# DIOT_Kasli_Adapter.net
KiCad netlist of a schematic drawn in Altium Designer
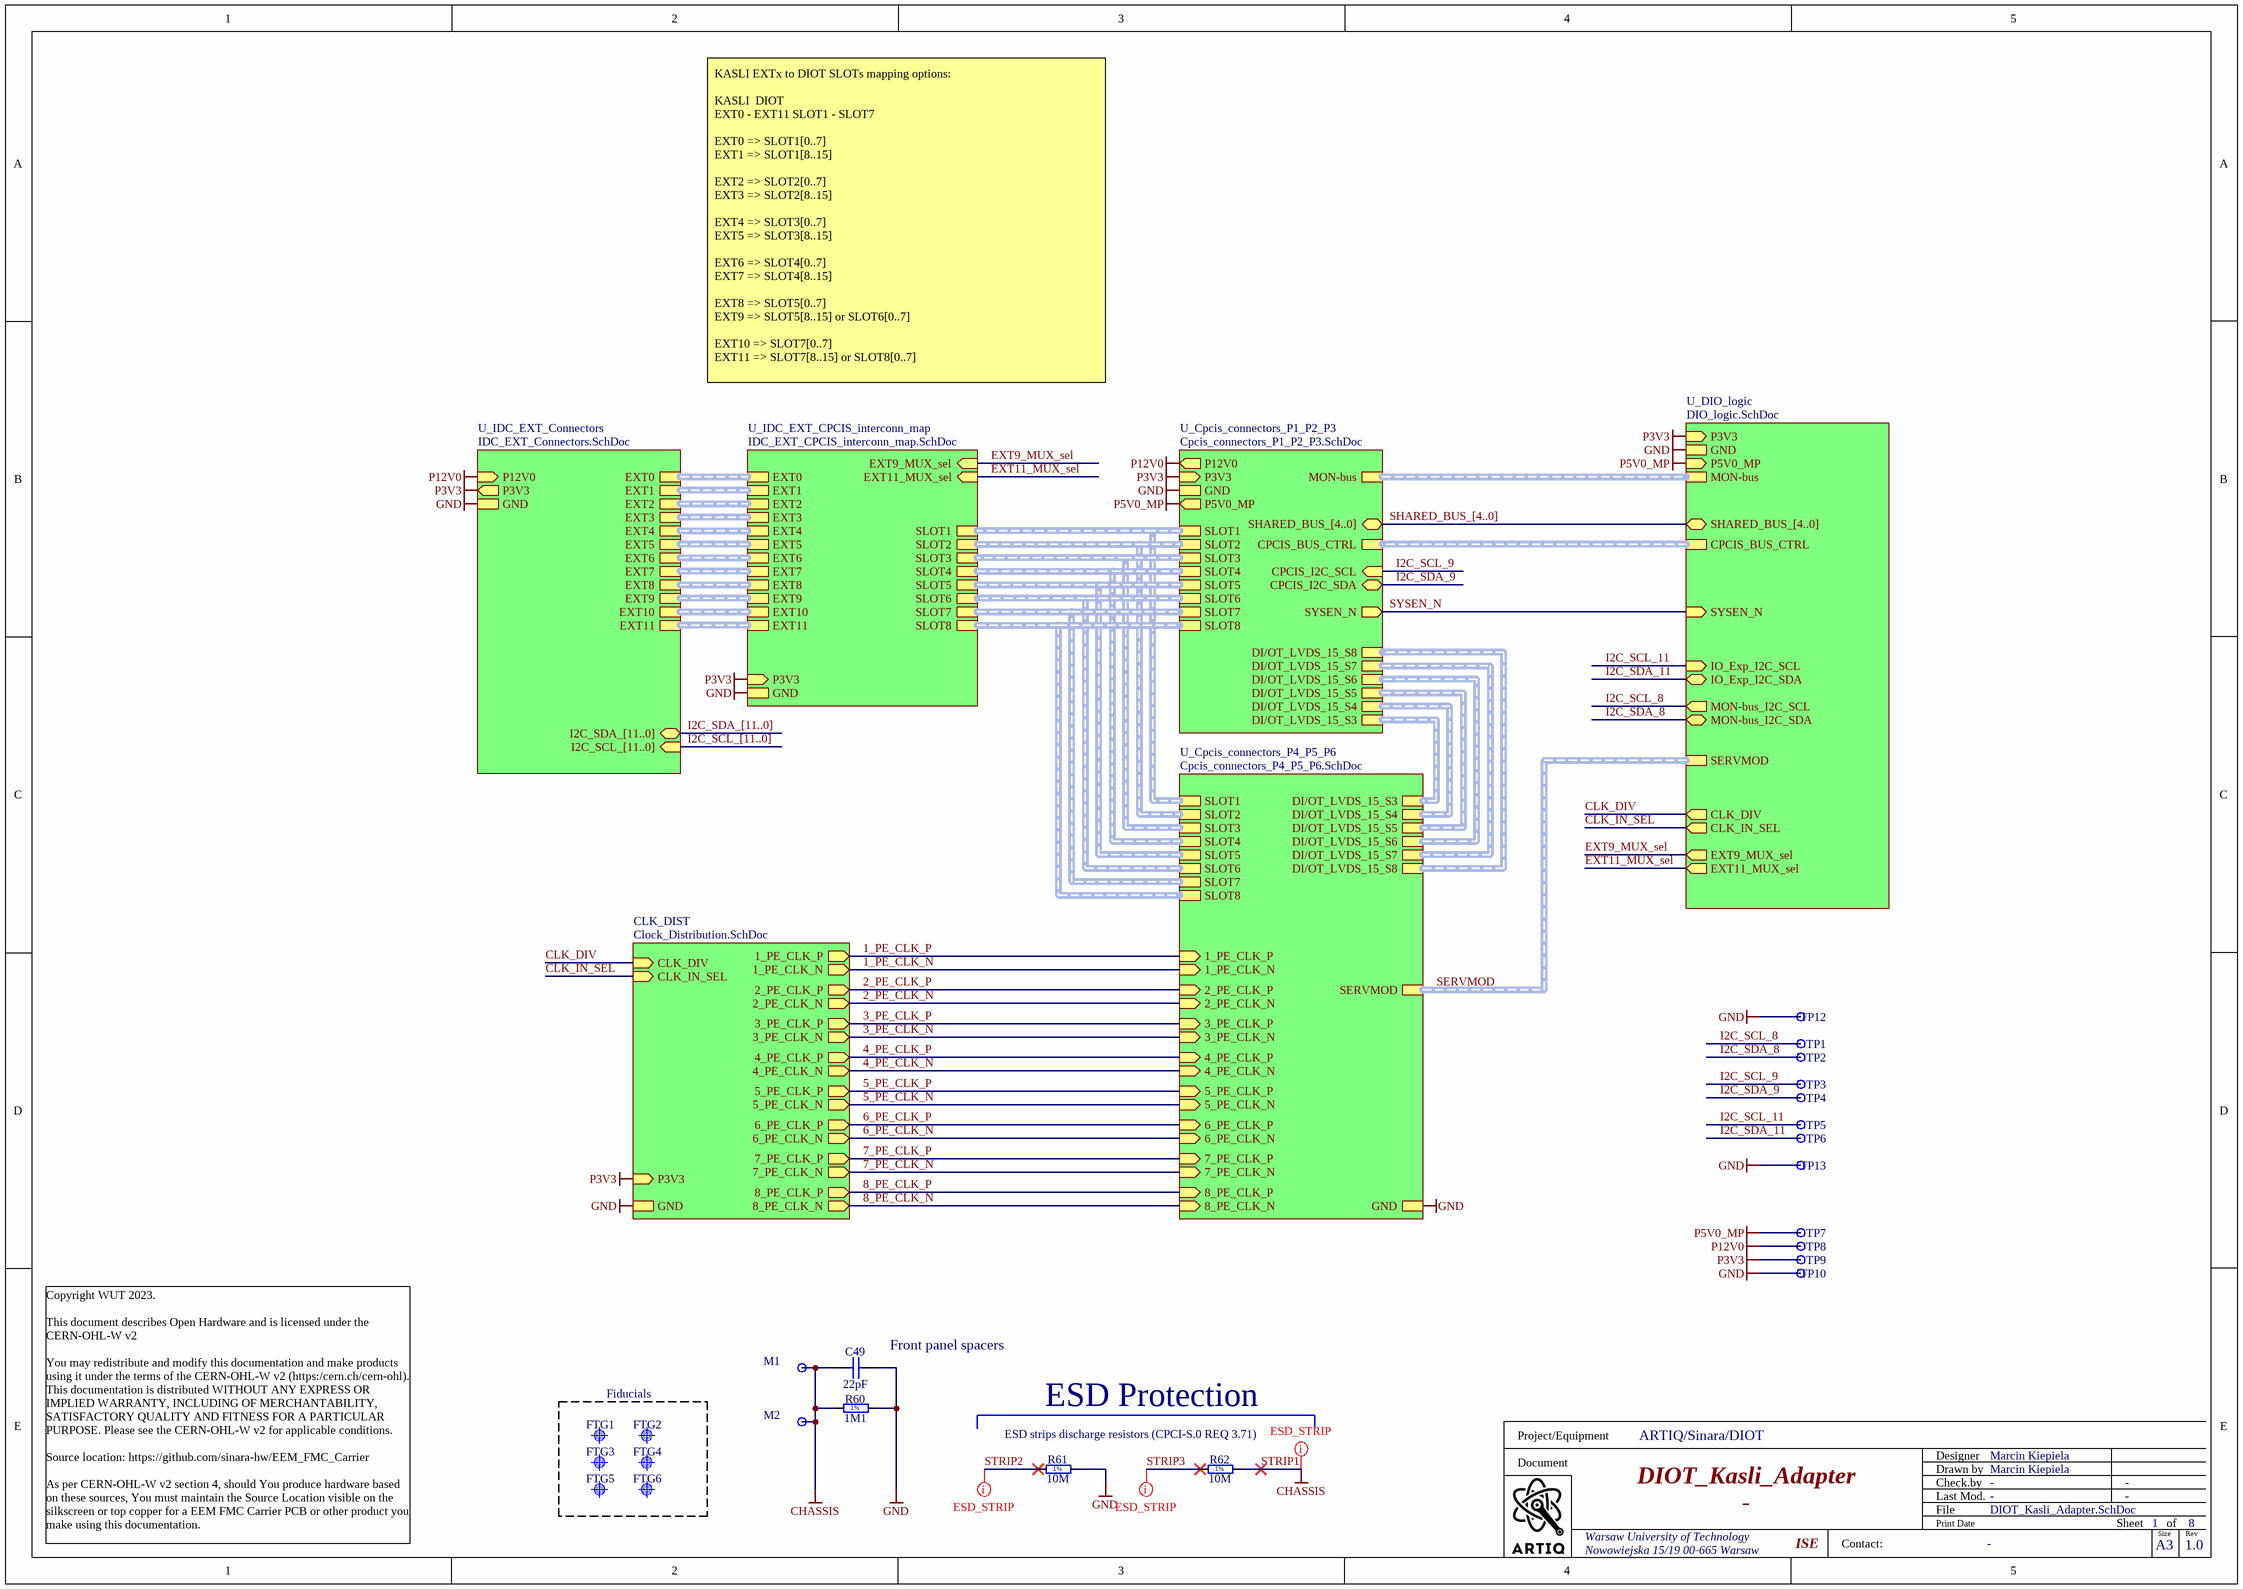
[diagram p0: DIOT_Kasli_Adapter.SchDoc]

(export (version "E")
  (design (tool "Eeschema 10.0.6"))
  (components
    (comp (ref "C49")
      (value "22pF")
      (footprint "CAPC1005X55N")
      (description "Non-polarised capacitor")
      (fields
        (field (name "PART NUMBER") "CC0402_22PF_50V_5%_C0G")
        (field (name "VOLTAGE") "50V")
        (field (name "AUTHOR") "CERN DEM JLC")
      )
      (libsource (lib "Capacitors") (part "Capacitor - non polarized"))
    )
    (comp (ref "FTG1")
      (value "Use only in PCB")
      (footprint "FIDUCIAL_TOP_S100-200")
      (description "Fiducial Target")
      (fields (field (name "PART NUMBER") "FIDUCIAL_TARGET_S100-200") (field (name "AUTHOR") "CERN DEM JLC"))
      (libsource (lib "Eletro-mechanical") (part "Fiducial Target"))
    )
    (comp (ref "FTG2")
      (value "Use only in PCB")
      (footprint "FIDUCIAL_TOP_S100-200")
      (description "Fiducial Target")
      (fields (field (name "PART NUMBER") "FIDUCIAL_TARGET_S100-200") (field (name "AUTHOR") "CERN DEM JLC"))
      (libsource (lib "Eletro-mechanical") (part "Fiducial Target"))
    )
    (comp (ref "FTG3")
      (value "Use only in PCB")
      (footprint "FIDUCIAL_TOP_S100-200")
      (description "Fiducial Target")
      (fields (field (name "PART NUMBER") "FIDUCIAL_TARGET_S100-200") (field (name "AUTHOR") "CERN DEM JLC"))
      (libsource (lib "Eletro-mechanical") (part "Fiducial Target"))
    )
    (comp (ref "FTG4")
      (value "Use only in PCB")
      (footprint "FIDUCIAL_TOP_S100-200")
      (description "Fiducial Target")
      (fields (field (name "PART NUMBER") "FIDUCIAL_TARGET_S100-200") (field (name "AUTHOR") "CERN DEM JLC"))
      (libsource (lib "Eletro-mechanical") (part "Fiducial Target"))
    )
    (comp (ref "FTG5")
      (value "Use only in PCB")
      (footprint "FIDUCIAL_TOP_S100-200")
      (description "Fiducial Target")
      (fields (field (name "PART NUMBER") "FIDUCIAL_TARGET_S100-200") (field (name "AUTHOR") "CERN DEM JLC"))
      (libsource (lib "Eletro-mechanical") (part "Fiducial Target"))
    )
    (comp (ref "FTG6")
      (value "Use only in PCB")
      (footprint "FIDUCIAL_TOP_S100-200")
      (description "Fiducial Target")
      (fields (field (name "PART NUMBER") "FIDUCIAL_TARGET_S100-200") (field (name "AUTHOR") "CERN DEM JLC"))
      (libsource (lib "Eletro-mechanical") (part "Fiducial Target"))
    )
    (comp (ref "M1")
      (value "Plated Hole")
      (footprint "MTG300_600")
      (description "Single Terminal Socket")
      (fields (field (name "PART NUMBER") "PLATED_HOLE3.0_PAD6.0") (field (name "AUTHOR") "CERN DEM JLC"))
      (libsource (lib "Eletro-mechanical") (part "Single Terminal Socket"))
    )
    (comp (ref "M2")
      (value "Plated Hole")
      (footprint "MTG300_600")
      (description "Single Terminal Socket")
      (fields (field (name "PART NUMBER") "PLATED_HOLE3.0_PAD6.0") (field (name "AUTHOR") "CERN DEM JLC"))
      (libsource (lib "Eletro-mechanical") (part "Single Terminal Socket"))
    )
    (comp (ref "R60")
      (value "1M1")
      (footprint "RESC2012X60N")
      (description "Resistor - 1%")
      (fields
        (field (name "PART NUMBER") "R0805_1M1_1%_0.125W_100PPM")
        (field (name "POWER") "0.125W")
        (field (name "AUTHOR") "CERN DEM JLC")
      )
      (libsource (lib "Resistors") (part "Resistor - 1%"))
    )
    (comp (ref "R61")
      (value "10M")
      (footprint "RESC2113X55N")
      (description "Resistor - 1%")
      (fields
        (field (name "PART NUMBER") "R0805_10M_1%_0.125W_100PPM_VISHAY_CRCW e3")
        (field (name "POWER") "0.125W")
        (field (name "AUTHOR") "CERN DEM BC")
      )
      (libsource (lib "Resistors") (part "Resistor - 1%"))
    )
    (comp (ref "R62")
      (value "10M")
      (footprint "RESC2113X55N")
      (description "Resistor - 1%")
      (fields
        (field (name "PART NUMBER") "R0805_10M_1%_0.125W_100PPM_VISHAY_CRCW e3")
        (field (name "POWER") "0.125W")
        (field (name "AUTHOR") "CERN DEM BC")
      )
      (libsource (lib "Resistors") (part "Resistor - 1%"))
    )
    (comp (ref "TP1")
      (value "P3V3")
      (footprint "TPS127")
      (description "Test Point")
      (fields (field (name "PART NUMBER") "SMD_PAD_1.27X1.27MM") (field (name "AUTHOR") "CERN DEM JLC"))
      (libsource (lib "Eletro-mechanical") (part "Test Point"))
    )
    (comp (ref "TP2")
      (value "P3V3")
      (footprint "TPS127")
      (description "Test Point")
      (fields (field (name "PART NUMBER") "SMD_PAD_1.27X1.27MM") (field (name "AUTHOR") "CERN DEM JLC"))
      (libsource (lib "Eletro-mechanical") (part "Test Point"))
    )
    (comp (ref "TP3")
      (value "P3V3")
      (footprint "TPS127")
      (description "Test Point")
      (fields (field (name "PART NUMBER") "SMD_PAD_1.27X1.27MM") (field (name "AUTHOR") "CERN DEM JLC"))
      (libsource (lib "Eletro-mechanical") (part "Test Point"))
    )
    (comp (ref "TP4")
      (value "P3V3")
      (footprint "TPS127")
      (description "Test Point")
      (fields (field (name "PART NUMBER") "SMD_PAD_1.27X1.27MM") (field (name "AUTHOR") "CERN DEM JLC"))
      (libsource (lib "Eletro-mechanical") (part "Test Point"))
    )
    (comp (ref "TP5")
      (value "P3V3")
      (footprint "TPS127")
      (description "Test Point")
      (fields (field (name "PART NUMBER") "SMD_PAD_1.27X1.27MM") (field (name "AUTHOR") "CERN DEM JLC"))
      (libsource (lib "Eletro-mechanical") (part "Test Point"))
    )
    (comp (ref "TP6")
      (value "P3V3")
      (footprint "TPS127")
      (description "Test Point")
      (fields (field (name "PART NUMBER") "SMD_PAD_1.27X1.27MM") (field (name "AUTHOR") "CERN DEM JLC"))
      (libsource (lib "Eletro-mechanical") (part "Test Point"))
    )
    (comp (ref "TP7")
      (value "P3V3")
      (footprint "TPS127")
      (description "Test Point")
      (fields (field (name "PART NUMBER") "SMD_PAD_1.27X1.27MM") (field (name "AUTHOR") "CERN DEM JLC"))
      (libsource (lib "Eletro-mechanical") (part "Test Point"))
    )
    (comp (ref "TP8")
      (value "P3V3")
      (footprint "TPS127")
      (description "Test Point")
      (fields (field (name "PART NUMBER") "SMD_PAD_1.27X1.27MM") (field (name "AUTHOR") "CERN DEM JLC"))
      (libsource (lib "Eletro-mechanical") (part "Test Point"))
    )
    (comp (ref "TP9")
      (value "P3V3")
      (footprint "TPS127")
      (description "Test Point")
      (fields (field (name "PART NUMBER") "SMD_PAD_1.27X1.27MM") (field (name "AUTHOR") "CERN DEM JLC"))
      (libsource (lib "Eletro-mechanical") (part "Test Point"))
    )
    (comp (ref "TP10")
      (value "P3V3")
      (footprint "TPS127")
      (description "Test Point")
      (fields (field (name "PART NUMBER") "SMD_PAD_1.27X1.27MM") (field (name "AUTHOR") "CERN DEM JLC"))
      (libsource (lib "Eletro-mechanical") (part "Test Point"))
    )
    (comp (ref "TP12")
      (value "P3V3")
      (footprint "TPS127")
      (description "Test Point")
      (fields (field (name "PART NUMBER") "SMD_PAD_1.27X1.27MM") (field (name "AUTHOR") "CERN DEM JLC"))
      (libsource (lib "Eletro-mechanical") (part "Test Point"))
    )
    (comp (ref "TP13")
      (value "P3V3")
      (footprint "TPS127")
      (description "Test Point")
      (fields (field (name "PART NUMBER") "SMD_PAD_1.27X1.27MM") (field (name "AUTHOR") "CERN DEM JLC"))
      (libsource (lib "Eletro-mechanical") (part "Test Point"))
    )
  )
  (nets
    (net (code "64") (name "/I2C_SCL_8") (class "Default")
      (node (ref "TP1") (pin "1") (pinfunction "1_1") (pintype "bidirectional"))
    )
    (net (code "65") (name "/I2C_SCL_9") (class "Default")
      (node (ref "TP3") (pin "1") (pinfunction "1_1") (pintype "bidirectional"))
    )
    (net (code "66") (name "/I2C_SCL_11") (class "Default")
      (node (ref "TP5") (pin "1") (pinfunction "1_1") (pintype "bidirectional"))
    )
    (net (code "68") (name "/I2C_SDA_8") (class "Default")
      (node (ref "TP2") (pin "1") (pinfunction "1_1") (pintype "bidirectional"))
    )
    (net (code "69") (name "/I2C_SDA_9") (class "Default")
      (node (ref "TP4") (pin "1") (pinfunction "1_1") (pintype "bidirectional"))
    )
    (net (code "70") (name "/I2C_SDA_11") (class "Default")
      (node (ref "TP6") (pin "1") (pinfunction "1_1") (pintype "bidirectional"))
    )
    (net (code "83") (name "/STRIP2") (class "Default")
      (node (ref "R61") (pin "1") (pinfunction "1_1") (pintype "passive+no_connect"))
    )
    (net (code "84") (name "/STRIP3") (class "Default")
      (node (ref "R62") (pin "1") (pinfunction "1_1") (pintype "passive+no_connect"))
    )
    (net (code "87") (name "CHASSIS") (class "Default")
      (node (ref "C49") (pin "1") (pinfunction "1_1") (pintype "passive"))
      (node (ref "M1") (pin "1") (pinfunction "1_1") (pintype "bidirectional"))
      (node (ref "M2") (pin "1") (pinfunction "1_1") (pintype "bidirectional"))
      (node (ref "R60") (pin "1") (pinfunction "1_1") (pintype "passive"))
      (node (ref "R62") (pin "2") (pinfunction "2_2") (pintype "passive"))
    )
    (net (code "88") (name "GND") (class "Default")
      (node (ref "C49") (pin "2") (pinfunction "2_2") (pintype "passive"))
      (node (ref "R60") (pin "2") (pinfunction "2_2") (pintype "passive"))
      (node (ref "R61") (pin "2") (pinfunction "2_2") (pintype "passive"))
      (node (ref "TP10") (pin "1") (pinfunction "1_1") (pintype "bidirectional"))
      (node (ref "TP12") (pin "1") (pinfunction "1_1") (pintype "bidirectional"))
      (node (ref "TP13") (pin "1") (pinfunction "1_1") (pintype "bidirectional"))
    )
    (net (code "89") (name "P3V3") (class "Default")
      (node (ref "TP9") (pin "1") (pinfunction "1_1") (pintype "bidirectional"))
    )
    (net (code "90") (name "P5V0_MP") (class "Default")
      (node (ref "TP7") (pin "1") (pinfunction "1_1") (pintype "bidirectional"))
    )
    (net (code "91") (name "P12V0") (class "Default")
      (node (ref "TP8") (pin "1") (pinfunction "1_1") (pintype "bidirectional"))
    )
  )
)
